# freeduino_hs.net
KiCad netlist of a schematic drawn in EAGLE
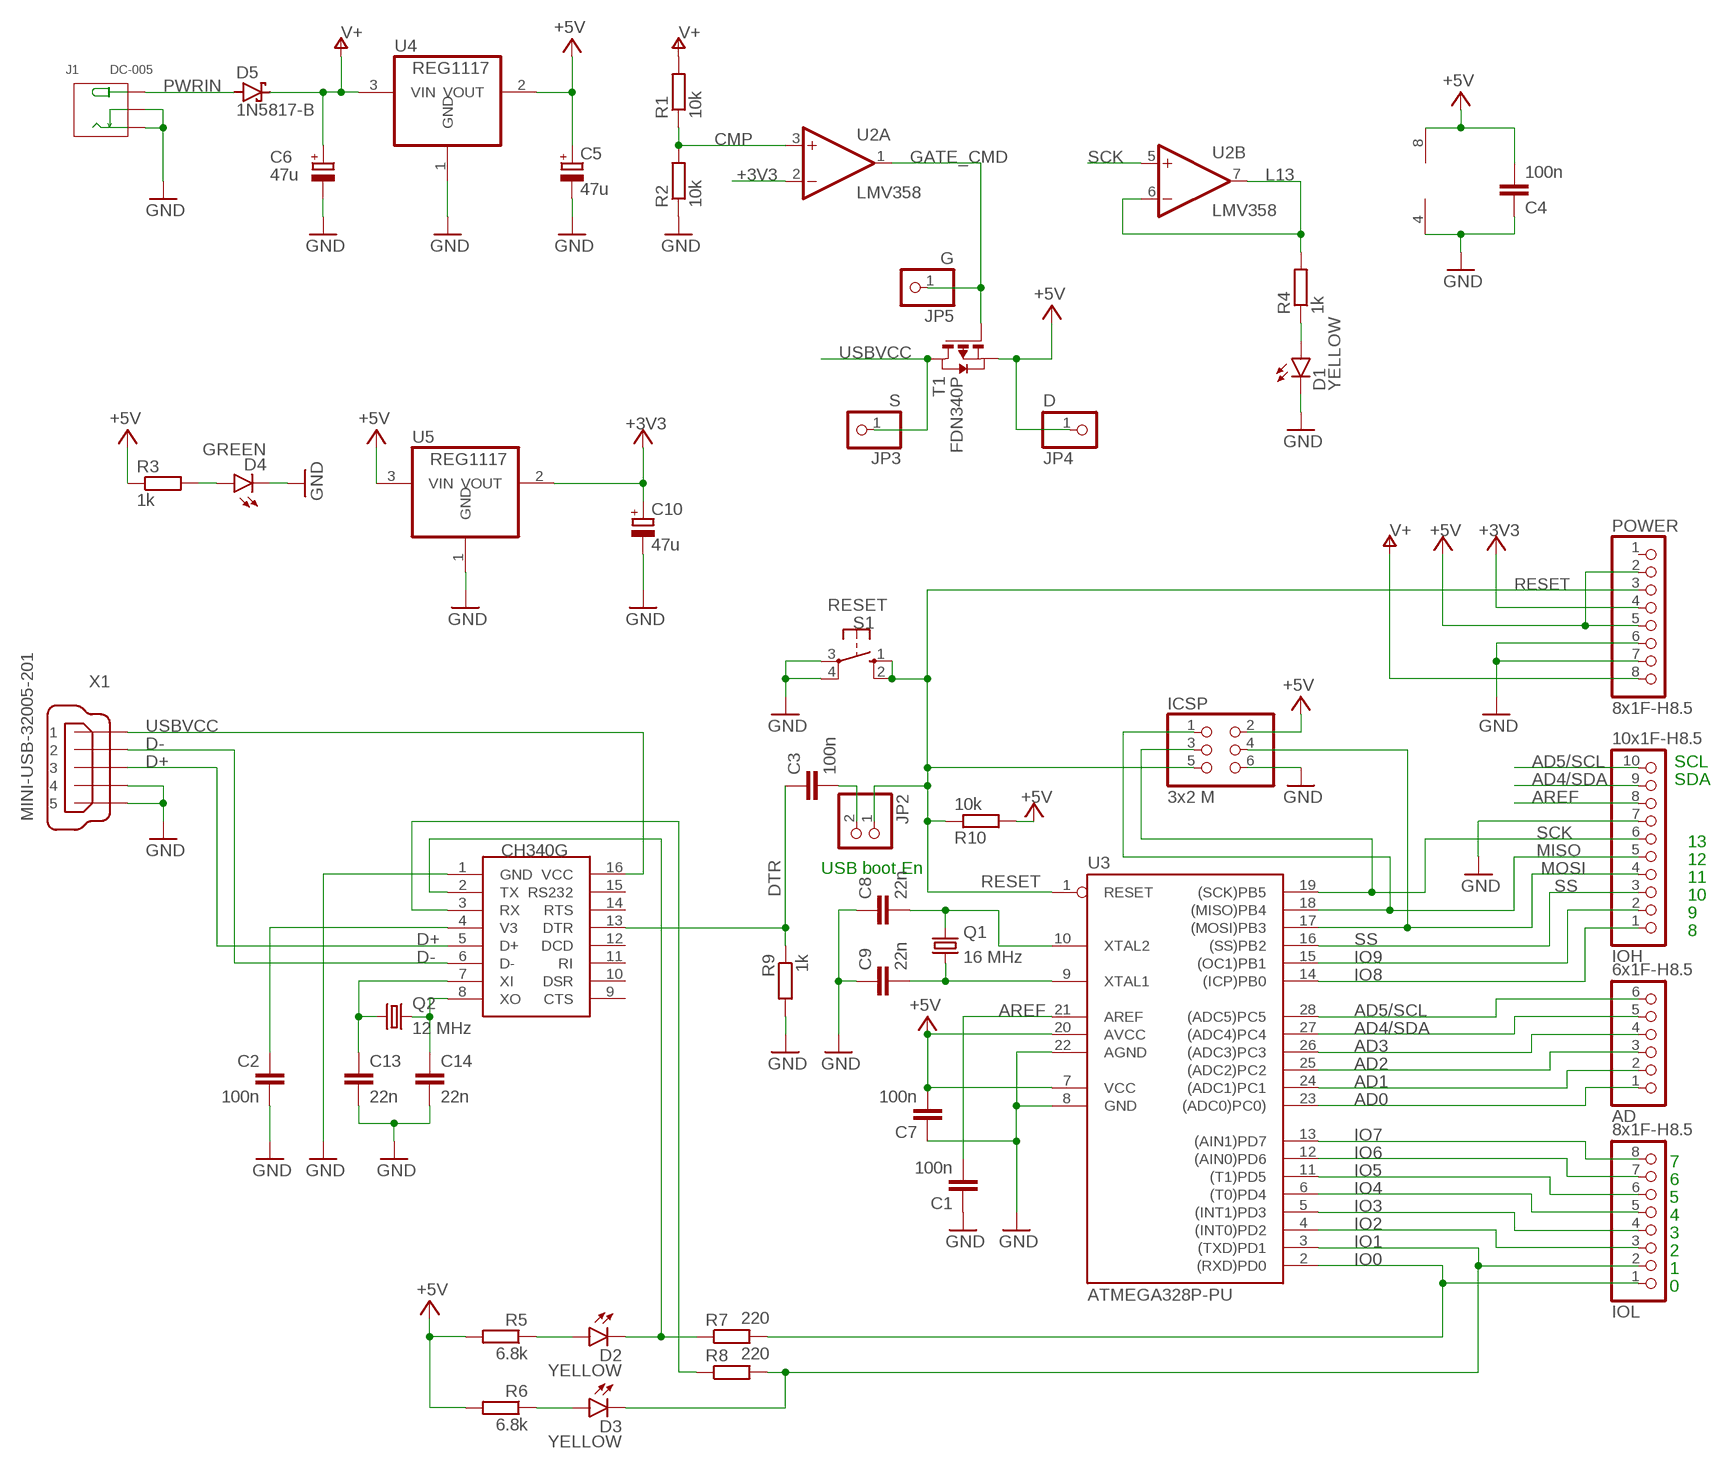
[diagram p0: schematic, sheet 1]

(export (version "E")
  (design (tool "Eeschema 10.0.6"))
  (components
    (comp (ref "AD")
      (value "6x1F-H8.5")
      (footprint "eagle-import:1X06")
      (libsource (lib "eagle-import") (part "PINHD-1X6"))
    )
    (comp (ref "C1")
      (value "100n")
      (footprint "eagle-import:C050-024X044")
      (libsource (lib "eagle-import") (part "C-EU050-024X044"))
    )
    (comp (ref "C2")
      (value "100n")
      (footprint "eagle-import:C050-024X044")
      (libsource (lib "eagle-import") (part "C-EU050-024X044"))
    )
    (comp (ref "C3")
      (value "100n")
      (footprint "eagle-import:C050-024X044")
      (libsource (lib "eagle-import") (part "C-EU050-024X044"))
    )
    (comp (ref "C4")
      (value "100n")
      (footprint "eagle-import:C050-024X044")
      (libsource (lib "eagle-import") (part "C-EU050-024X044"))
    )
    (comp (ref "C5")
      (value "47u")
      (footprint "eagle-import:E2,5-5")
      (libsource (lib "eagle-import") (part "CPOL-EUE2.5-5"))
    )
    (comp (ref "C6")
      (value "47u")
      (footprint "eagle-import:E2,5-5")
      (libsource (lib "eagle-import") (part "CPOL-EUE2.5-5"))
    )
    (comp (ref "C7")
      (value "100n")
      (footprint "eagle-import:C050-024X044")
      (libsource (lib "eagle-import") (part "C-EU050-024X044"))
    )
    (comp (ref "C8")
      (value "22n")
      (footprint "eagle-import:C050-024X044")
      (libsource (lib "eagle-import") (part "C-EU050-024X044"))
    )
    (comp (ref "C9")
      (value "22n")
      (footprint "eagle-import:C050-024X044")
      (libsource (lib "eagle-import") (part "C-EU050-024X044"))
    )
    (comp (ref "C10")
      (value "47u")
      (footprint "eagle-import:E2,5-5")
      (libsource (lib "eagle-import") (part "CPOL-EUE2.5-5"))
    )
    (comp (ref "C13")
      (value "22n")
      (footprint "eagle-import:C050-024X044")
      (libsource (lib "eagle-import") (part "C-EU050-024X044"))
    )
    (comp (ref "C14")
      (value "22n")
      (footprint "eagle-import:C050-024X044")
      (libsource (lib "eagle-import") (part "C-EU050-024X044"))
    )
    (comp (ref "D1")
      (value "YELLOW")
      (footprint "eagle-import:LED3MM")
      (libsource (lib "eagle-import") (part "LED3MM"))
    )
    (comp (ref "D2")
      (value "YELLOW")
      (footprint "eagle-import:LED3MM")
      (libsource (lib "eagle-import") (part "LED3MM"))
    )
    (comp (ref "D3")
      (value "YELLOW")
      (footprint "eagle-import:LED3MM")
      (libsource (lib "eagle-import") (part "LED3MM"))
    )
    (comp (ref "D4")
      (value "GREEN")
      (footprint "eagle-import:LED3MM")
      (libsource (lib "eagle-import") (part "LED3MM"))
    )
    (comp (ref "D5")
      (value "1N5817-B")
      (footprint "eagle-import:DO41-7.6")
      (libsource (lib "eagle-import") (part "1N5817-B"))
    )
    (comp (ref "ICSP")
      (value "3x2 M")
      (footprint "eagle-import:2X03")
      (libsource (lib "eagle-import") (part "PINHD-2X3"))
    )
    (comp (ref "IOH")
      (value "10x1F-H8.5")
      (footprint "eagle-import:1X10")
      (libsource (lib "eagle-import") (part "PINHD-1X10"))
    )
    (comp (ref "IOL")
      (value "8x1F-H8.5")
      (footprint "eagle-import:1X08")
      (libsource (lib "eagle-import") (part "PINHD-1X8"))
    )
    (comp (ref "J1")
      (value "DC-005")
      (footprint "eagle-import:DCJ3P-14.2X11.0X9.0MM")
      (libsource (lib "eagle-import") (part "CONN-POWER-JACK-2.1MM(DC-005)"))
    )
    (comp (ref "JP2")
      (value "PINHD-1X2")
      (footprint "eagle-import:1X02")
      (libsource (lib "eagle-import") (part "PINHD-1X2"))
    )
    (comp (ref "JP3")
      (value "S")
      (footprint "eagle-import:1X01")
      (libsource (lib "eagle-import") (part "PINHD-1X1"))
    )
    (comp (ref "JP4")
      (value "D")
      (footprint "eagle-import:1X01")
      (libsource (lib "eagle-import") (part "PINHD-1X1"))
    )
    (comp (ref "JP5")
      (value "G")
      (footprint "eagle-import:1X01")
      (libsource (lib "eagle-import") (part "PINHD-1X1"))
    )
    (comp (ref "POWER")
      (value "8x1F-H8.5")
      (footprint "eagle-import:1X08")
      (libsource (lib "eagle-import") (part "PINHD-1X8"))
    )
    (comp (ref "Q1")
      (value "16 MHz")
      (footprint "eagle-import:HC49_S")
      (libsource (lib "eagle-import") (part "CRYSTALHC49S"))
    )
    (comp (ref "Q2")
      (value "12 MHz")
      (footprint "eagle-import:HC49_S")
      (libsource (lib "eagle-import") (part "CRYSTALHC49S"))
    )
    (comp (ref "R1")
      (value "10k")
      (footprint "eagle-import:0204_7")
      (libsource (lib "eagle-import") (part "R-EU_0204/7"))
    )
    (comp (ref "R2")
      (value "10k")
      (footprint "eagle-import:0204_7")
      (libsource (lib "eagle-import") (part "R-EU_0204/7"))
    )
    (comp (ref "R3")
      (value "1k")
      (footprint "eagle-import:0204_7")
      (libsource (lib "eagle-import") (part "R-EU_0204/7"))
    )
    (comp (ref "R4")
      (value "1k")
      (footprint "eagle-import:0204_7")
      (libsource (lib "eagle-import") (part "R-EU_0204/7"))
    )
    (comp (ref "R5")
      (value "6.8k")
      (footprint "eagle-import:0204_7")
      (libsource (lib "eagle-import") (part "R-EU_0204/7"))
    )
    (comp (ref "R6")
      (value "6.8k")
      (footprint "eagle-import:0204_7")
      (libsource (lib "eagle-import") (part "R-EU_0204/7"))
    )
    (comp (ref "R7")
      (value "220")
      (footprint "eagle-import:0204_7")
      (libsource (lib "eagle-import") (part "R-EU_0204/7"))
    )
    (comp (ref "R8")
      (value "220")
      (footprint "eagle-import:0204_7")
      (libsource (lib "eagle-import") (part "R-EU_0204/7"))
    )
    (comp (ref "R9")
      (value "1k")
      (footprint "eagle-import:0204_7")
      (libsource (lib "eagle-import") (part "R-EU_0204/7"))
    )
    (comp (ref "R10")
      (value "10k")
      (footprint "eagle-import:0204_7")
      (libsource (lib "eagle-import") (part "R-EU_0204/7"))
    )
    (comp (ref "S1")
      (value "RESET")
      (footprint "eagle-import:B3F-10XX")
      (fields (field (name "MPN") "B3F-1000"))
      (libsource (lib "eagle-import") (part "10-XX"))
    )
    (comp (ref "T1")
      (value "FDN340P")
      (footprint "eagle-import:SOT-23")
      (libsource (lib "eagle-import") (part "PMOSSOT23"))
    )
    (comp (ref "U1")
      (value "CH340G")
      (footprint "eagle-import:SOIC16")
      (libsource (lib "eagle-import") (part "CH340G"))
    )
    (comp (ref "U2")
      (value "LMV358")
      (footprint "eagle-import:SO08")
      (libsource (lib "eagle-import") (part "LMV358?M"))
    )
    (comp (ref "U3")
      (value "ATMEGA328P-PU")
      (footprint "eagle-import:DIL28-3")
      (libsource (lib "eagle-import") (part "ATMEGA328P-PU"))
    )
    (comp (ref "U4")
      (value "REG1117")
      (footprint "eagle-import:SOT223")
      (libsource (lib "eagle-import") (part "REG1117"))
    )
    (comp (ref "U5")
      (value "REG1117")
      (footprint "eagle-import:SOT223")
      (libsource (lib "eagle-import") (part "REG1117"))
    )
    (comp (ref "X1")
      (value "MINI-USB-32005-201")
      (footprint "eagle-import:32005-201")
      (libsource (lib "eagle-import") (part "MINI-USB-32005-201"))
    )
  )
  (nets
    (net (code "1") (name "+3V3") (class "Default")
      (node (ref "C10") (pin "+") (pinfunction "+_+") (pintype "passive"))
      (node (ref "POWER") (pin "4") (pinfunction "4_4") (pintype "passive"))
      (node (ref "U2") (pin "2") (pinfunction "-IN_2") (pintype "input"))
      (node (ref "U5") (pin "2") (pinfunction "VOUT_2") (pintype "output"))
    )
    (net (code "2") (name "+5V") (class "Default")
      (node (ref "C4") (pin "2") (pinfunction "2_2") (pintype "passive"))
      (node (ref "C5") (pin "+") (pinfunction "+_+") (pintype "passive"))
      (node (ref "C7") (pin "2") (pinfunction "2_2") (pintype "passive"))
      (node (ref "ICSP") (pin "2") (pinfunction "2_2") (pintype "passive"))
      (node (ref "JP4") (pin "1") (pinfunction "1_1") (pintype "passive"))
      (node (ref "POWER") (pin "2") (pinfunction "2_2") (pintype "passive"))
      (node (ref "POWER") (pin "5") (pinfunction "5_5") (pintype "passive"))
      (node (ref "R10") (pin "2") (pinfunction "2_2") (pintype "passive"))
      (node (ref "R3") (pin "1") (pinfunction "1_1") (pintype "passive"))
      (node (ref "R5") (pin "2") (pinfunction "2_2") (pintype "passive"))
      (node (ref "R6") (pin "2") (pinfunction "2_2") (pintype "passive"))
      (node (ref "T1") (pin "2") (pinfunction "S_2") (pintype "passive"))
      (node (ref "U2") (pin "8") (pinfunction "V+_8") (pintype "power_in"))
      (node (ref "U3") (pin "20") (pinfunction "AVCC_20") (pintype "power_in"))
      (node (ref "U3") (pin "7") (pinfunction "VCC_7") (pintype "power_in"))
      (node (ref "U4") (pin "2") (pinfunction "VOUT_2") (pintype "output"))
      (node (ref "U5") (pin "3") (pinfunction "VIN_3") (pintype "input"))
    )
    (net (code "3") (name "/AD0") (class "Default")
      (node (ref "AD") (pin "1") (pinfunction "1_1") (pintype "passive"))
      (node (ref "U3") (pin "23") (pinfunction "(ADC0)PC0)_23") (pintype "bidirectional"))
    )
    (net (code "4") (name "/AD1") (class "Default")
      (node (ref "AD") (pin "2") (pinfunction "2_2") (pintype "passive"))
      (node (ref "U3") (pin "24") (pinfunction "(ADC1)PC1_24") (pintype "bidirectional"))
    )
    (net (code "5") (name "/AD2") (class "Default")
      (node (ref "AD") (pin "3") (pinfunction "3_3") (pintype "passive"))
      (node (ref "U3") (pin "25") (pinfunction "(ADC2)PC2_25") (pintype "bidirectional"))
    )
    (net (code "6") (name "/AD3") (class "Default")
      (node (ref "AD") (pin "4") (pinfunction "4_4") (pintype "passive"))
      (node (ref "U3") (pin "26") (pinfunction "(ADC3)PC3_26") (pintype "bidirectional"))
    )
    (net (code "7") (name "/AD4{slash}SDA") (class "Default")
      (node (ref "AD") (pin "5") (pinfunction "5_5") (pintype "passive"))
      (node (ref "IOH") (pin "9") (pinfunction "9_9") (pintype "passive"))
      (node (ref "U3") (pin "27") (pinfunction "(ADC4)PC4_27") (pintype "bidirectional"))
    )
    (net (code "8") (name "/AD5{slash}SCL") (class "Default")
      (node (ref "AD") (pin "6") (pinfunction "6_6") (pintype "passive"))
      (node (ref "IOH") (pin "10") (pinfunction "10_10") (pintype "passive"))
      (node (ref "U3") (pin "28") (pinfunction "(ADC5)PC5_28") (pintype "bidirectional"))
    )
    (net (code "9") (name "/AREF") (class "Default")
      (node (ref "C1") (pin "2") (pinfunction "2_2") (pintype "passive"))
      (node (ref "IOH") (pin "8") (pinfunction "8_8") (pintype "passive"))
      (node (ref "U3") (pin "21") (pinfunction "AREF_21") (pintype "passive"))
    )
    (net (code "10") (name "/CMP") (class "Default")
      (node (ref "R1") (pin "1") (pinfunction "1_1") (pintype "passive"))
      (node (ref "R2") (pin "2") (pinfunction "2_2") (pintype "passive"))
      (node (ref "U2") (pin "3") (pinfunction "+IN_3") (pintype "input"))
    )
    (net (code "11") (name "/D+") (class "Default")
      (node (ref "U1") (pin "5") (pinfunction "D+_5") (pintype "bidirectional"))
      (node (ref "X1") (pin "3") (pinfunction "3_3") (pintype "passive"))
    )
    (net (code "12") (name "/D-") (class "Default")
      (node (ref "U1") (pin "6") (pinfunction "D-_6") (pintype "bidirectional"))
      (node (ref "X1") (pin "2") (pinfunction "2_2") (pintype "passive"))
    )
    (net (code "13") (name "/DTR") (class "Default")
      (node (ref "C3") (pin "1") (pinfunction "1_1") (pintype "passive"))
      (node (ref "R9") (pin "1") (pinfunction "1_1") (pintype "passive"))
      (node (ref "U1") (pin "13") (pinfunction "DTR_13") (pintype "bidirectional"))
    )
    (net (code "14") (name "/GATE_CMD") (class "Default")
      (node (ref "JP5") (pin "1") (pinfunction "1_1") (pintype "passive"))
      (node (ref "T1") (pin "3") (pinfunction "G_3") (pintype "passive"))
      (node (ref "U2") (pin "1") (pinfunction "OUT_1") (pintype "output"))
    )
    (net (code "15") (name "/IO0") (class "Default")
      (node (ref "IOL") (pin "1") (pinfunction "1_1") (pintype "passive"))
      (node (ref "R7") (pin "2") (pinfunction "2_2") (pintype "passive"))
      (node (ref "U3") (pin "2") (pinfunction "(RXD)PD0_2") (pintype "bidirectional"))
    )
    (net (code "16") (name "/IO1") (class "Default")
      (node (ref "D3") (pin "K") (pinfunction "C_K") (pintype "passive"))
      (node (ref "IOL") (pin "2") (pinfunction "2_2") (pintype "passive"))
      (node (ref "R8") (pin "2") (pinfunction "2_2") (pintype "passive"))
      (node (ref "U3") (pin "3") (pinfunction "(TXD)PD1_3") (pintype "bidirectional"))
    )
    (net (code "17") (name "/IO2") (class "Default")
      (node (ref "IOL") (pin "3") (pinfunction "3_3") (pintype "passive"))
      (node (ref "U3") (pin "4") (pinfunction "(INT0)PD2_4") (pintype "bidirectional"))
    )
    (net (code "18") (name "/IO3") (class "Default")
      (node (ref "IOL") (pin "4") (pinfunction "4_4") (pintype "passive"))
      (node (ref "U3") (pin "5") (pinfunction "(INT1)PD3_5") (pintype "bidirectional"))
    )
    (net (code "19") (name "/IO4") (class "Default")
      (node (ref "IOL") (pin "5") (pinfunction "5_5") (pintype "passive"))
      (node (ref "U3") (pin "6") (pinfunction "(T0)PD4_6") (pintype "bidirectional"))
    )
    (net (code "20") (name "/IO5") (class "Default")
      (node (ref "IOL") (pin "6") (pinfunction "6_6") (pintype "passive"))
      (node (ref "U3") (pin "11") (pinfunction "(T1)PD5_11") (pintype "bidirectional"))
    )
    (net (code "21") (name "/IO6") (class "Default")
      (node (ref "IOL") (pin "7") (pinfunction "7_7") (pintype "passive"))
      (node (ref "U3") (pin "12") (pinfunction "(AIN0)PD6_12") (pintype "bidirectional"))
    )
    (net (code "22") (name "/IO7") (class "Default")
      (node (ref "IOL") (pin "8") (pinfunction "8_8") (pintype "passive"))
      (node (ref "U3") (pin "13") (pinfunction "(AIN1)PD7_13") (pintype "bidirectional"))
    )
    (net (code "23") (name "/IO8") (class "Default")
      (node (ref "IOH") (pin "1") (pinfunction "1_1") (pintype "passive"))
      (node (ref "U3") (pin "14") (pinfunction "(ICP)PB0_14") (pintype "bidirectional"))
    )
    (net (code "24") (name "/IO9") (class "Default")
      (node (ref "IOH") (pin "2") (pinfunction "2_2") (pintype "passive"))
      (node (ref "U3") (pin "15") (pinfunction "(OC1)PB1_15") (pintype "bidirectional"))
    )
    (net (code "25") (name "/L13") (class "Default")
      (node (ref "R4") (pin "2") (pinfunction "2_2") (pintype "passive"))
      (node (ref "U2") (pin "6") (pinfunction "-IN_6") (pintype "input"))
      (node (ref "U2") (pin "7") (pinfunction "OUT_7") (pintype "output"))
    )
    (net (code "26") (name "/MISO") (class "Default")
      (node (ref "ICSP") (pin "1") (pinfunction "1_1") (pintype "passive"))
      (node (ref "IOH") (pin "5") (pinfunction "5_5") (pintype "passive"))
      (node (ref "U3") (pin "18") (pinfunction "(MISO)PB4_18") (pintype "bidirectional"))
    )
    (net (code "27") (name "/MOSI") (class "Default")
      (node (ref "ICSP") (pin "4") (pinfunction "4_4") (pintype "passive"))
      (node (ref "IOH") (pin "4") (pinfunction "4_4") (pintype "passive"))
      (node (ref "U3") (pin "17") (pinfunction "(MOSI)PB3_17") (pintype "bidirectional"))
    )
    (net (code "28") (name "/PWRIN") (class "Default")
      (node (ref "D5") (pin "A") (pinfunction "A_A") (pintype "passive"))
      (node (ref "J1") (pin "+") (pinfunction "+_+") (pintype "bidirectional"))
    )
    (net (code "29") (name "/RESET") (class "Default")
      (node (ref "ICSP") (pin "5") (pinfunction "5_5") (pintype "passive"))
      (node (ref "JP2") (pin "1") (pinfunction "1_1") (pintype "passive"))
      (node (ref "POWER") (pin "3") (pinfunction "3_3") (pintype "passive"))
      (node (ref "R10") (pin "1") (pinfunction "1_1") (pintype "passive"))
      (node (ref "S1") (pin "1") (pinfunction "S_1") (pintype "passive"))
      (node (ref "S1") (pin "2") (pinfunction "S1_2") (pintype "passive"))
      (node (ref "U3") (pin "1") (pinfunction "RESET_1") (pintype "input"))
    )
    (net (code "30") (name "/SCK") (class "Default")
      (node (ref "ICSP") (pin "3") (pinfunction "3_3") (pintype "passive"))
      (node (ref "IOH") (pin "6") (pinfunction "6_6") (pintype "passive"))
      (node (ref "U2") (pin "5") (pinfunction "+IN_5") (pintype "input"))
      (node (ref "U3") (pin "19") (pinfunction "(SCK)PB5_19") (pintype "bidirectional"))
    )
    (net (code "31") (name "/SS") (class "Default")
      (node (ref "IOH") (pin "3") (pinfunction "3_3") (pintype "passive"))
      (node (ref "U3") (pin "16") (pinfunction "(SS)PB2_16") (pintype "bidirectional"))
    )
    (net (code "32") (name "/USBVCC") (class "Default")
      (node (ref "JP3") (pin "1") (pinfunction "1_1") (pintype "passive"))
      (node (ref "T1") (pin "1") (pinfunction "D_1") (pintype "passive"))
      (node (ref "U1") (pin "16") (pinfunction "VCC_16") (pintype "bidirectional"))
      (node (ref "X1") (pin "1") (pinfunction "1_1") (pintype "passive"))
    )
    (net (code "33") (name "GND") (class "Default")
      (node (ref "C1") (pin "1") (pinfunction "1_1") (pintype "passive"))
      (node (ref "C10") (pin "-") (pinfunction "-_-") (pintype "passive"))
      (node (ref "C13") (pin "2") (pinfunction "2_2") (pintype "passive"))
      (node (ref "C14") (pin "2") (pinfunction "2_2") (pintype "passive"))
      (node (ref "C2") (pin "2") (pinfunction "2_2") (pintype "passive"))
      (node (ref "C4") (pin "1") (pinfunction "1_1") (pintype "passive"))
      (node (ref "C5") (pin "-") (pinfunction "-_-") (pintype "passive"))
      (node (ref "C6") (pin "-") (pinfunction "-_-") (pintype "passive"))
      (node (ref "C7") (pin "1") (pinfunction "1_1") (pintype "passive"))
      (node (ref "C8") (pin "1") (pinfunction "1_1") (pintype "passive"))
      (node (ref "C9") (pin "1") (pinfunction "1_1") (pintype "passive"))
      (node (ref "D1") (pin "K") (pinfunction "C_K") (pintype "passive"))
      (node (ref "D4") (pin "K") (pinfunction "C_K") (pintype "passive"))
      (node (ref "ICSP") (pin "6") (pinfunction "6_6") (pintype "passive"))
      (node (ref "IOH") (pin "7") (pinfunction "7_7") (pintype "passive"))
      (node (ref "J1") (pin "-1") (pinfunction "-_-1") (pintype "bidirectional"))
      (node (ref "J1") (pin "-2") (pinfunction "CDN_-2") (pintype "bidirectional"))
      (node (ref "POWER") (pin "6") (pinfunction "6_6") (pintype "passive"))
      (node (ref "POWER") (pin "7") (pinfunction "7_7") (pintype "passive"))
      (node (ref "R2") (pin "1") (pinfunction "1_1") (pintype "passive"))
      (node (ref "R9") (pin "2") (pinfunction "2_2") (pintype "passive"))
      (node (ref "S1") (pin "3") (pinfunction "P_3") (pintype "passive"))
      (node (ref "S1") (pin "4") (pinfunction "P1_4") (pintype "passive"))
      (node (ref "U1") (pin "1") (pinfunction "GND_1") (pintype "bidirectional"))
      (node (ref "U2") (pin "4") (pinfunction "V-_4") (pintype "power_in"))
      (node (ref "U3") (pin "22") (pinfunction "AGND_22") (pintype "power_in"))
      (node (ref "U3") (pin "8") (pinfunction "GND_8") (pintype "power_in"))
      (node (ref "U4") (pin "1") (pinfunction "GND_1") (pintype "power_in"))
      (node (ref "U5") (pin "1") (pinfunction "GND_1") (pintype "power_in"))
      (node (ref "X1") (pin "4") (pinfunction "4_4") (pintype "passive"))
      (node (ref "X1") (pin "5") (pinfunction "5_5") (pintype "passive"))
    )
    (net (code "34") (name "Net-(C3-Pad2)") (class "Default")
      (node (ref "C3") (pin "2") (pinfunction "2_2") (pintype "passive"))
      (node (ref "JP2") (pin "2") (pinfunction "2_2") (pintype "passive"))
    )
    (net (code "35") (name "Net-(D1-PadA)") (class "Default")
      (node (ref "D1") (pin "A") (pinfunction "A_A") (pintype "passive"))
      (node (ref "R4") (pin "1") (pinfunction "1_1") (pintype "passive"))
    )
    (net (code "36") (name "Net-(D2-C)") (class "Default")
      (node (ref "D2") (pin "K") (pinfunction "C_K") (pintype "passive"))
      (node (ref "R7") (pin "1") (pinfunction "1_1") (pintype "passive"))
      (node (ref "U1") (pin "2") (pinfunction "TX_2") (pintype "bidirectional"))
    )
    (net (code "37") (name "Net-(D2-PadA)") (class "Default")
      (node (ref "D2") (pin "A") (pinfunction "A_A") (pintype "passive"))
      (node (ref "R5") (pin "1") (pinfunction "1_1") (pintype "passive"))
    )
    (net (code "38") (name "Net-(D3-PadA)") (class "Default")
      (node (ref "D3") (pin "A") (pinfunction "A_A") (pintype "passive"))
      (node (ref "R6") (pin "1") (pinfunction "1_1") (pintype "passive"))
    )
    (net (code "39") (name "Net-(D4-PadA)") (class "Default")
      (node (ref "D4") (pin "A") (pinfunction "A_A") (pintype "passive"))
      (node (ref "R3") (pin "2") (pinfunction "2_2") (pintype "passive"))
    )
    (net (code "40") (name "Net-(U1-RX)") (class "Default")
      (node (ref "R8") (pin "1") (pinfunction "1_1") (pintype "passive"))
      (node (ref "U1") (pin "3") (pinfunction "RX_3") (pintype "bidirectional"))
    )
    (net (code "41") (name "Net-(U1-V3)") (class "Default")
      (node (ref "C2") (pin "1") (pinfunction "1_1") (pintype "passive"))
      (node (ref "U1") (pin "4") (pinfunction "V3_4") (pintype "bidirectional"))
    )
    (net (code "42") (name "Net-(U1-XI)") (class "Default")
      (node (ref "C13") (pin "1") (pinfunction "1_1") (pintype "passive"))
      (node (ref "Q2") (pin "2") (pinfunction "2_2") (pintype "passive"))
      (node (ref "U1") (pin "7") (pinfunction "XI_7") (pintype "bidirectional"))
    )
    (net (code "43") (name "Net-(U1-XO)") (class "Default")
      (node (ref "C14") (pin "1") (pinfunction "1_1") (pintype "passive"))
      (node (ref "Q2") (pin "1") (pinfunction "1_1") (pintype "passive"))
      (node (ref "U1") (pin "8") (pinfunction "XO_8") (pintype "bidirectional"))
    )
    (net (code "44") (name "Net-(U3-XTAL1)") (class "Default")
      (node (ref "C9") (pin "2") (pinfunction "2_2") (pintype "passive"))
      (node (ref "Q1") (pin "1") (pinfunction "1_1") (pintype "passive"))
      (node (ref "U3") (pin "9") (pinfunction "XTAL1_9") (pintype "bidirectional"))
    )
    (net (code "45") (name "Net-(U3-XTAL2)") (class "Default")
      (node (ref "C8") (pin "2") (pinfunction "2_2") (pintype "passive"))
      (node (ref "Q1") (pin "2") (pinfunction "2_2") (pintype "passive"))
      (node (ref "U3") (pin "10") (pinfunction "XTAL2_10") (pintype "bidirectional"))
    )
    (net (code "46") (name "V+") (class "Default")
      (node (ref "C6") (pin "+") (pinfunction "+_+") (pintype "passive"))
      (node (ref "D5") (pin "C") (pinfunction "C_C") (pintype "passive"))
      (node (ref "POWER") (pin "8") (pinfunction "8_8") (pintype "passive"))
      (node (ref "R1") (pin "2") (pinfunction "2_2") (pintype "passive"))
      (node (ref "U4") (pin "3") (pinfunction "VIN_3") (pintype "input"))
    )
    (net (code "47") (name "unconnected-(POWER-Pad1)") (class "Default")
      (node (ref "POWER") (pin "1") (pinfunction "1_1") (pintype "passive"))
    )
    (net (code "48") (name "unconnected-(U1-CTS-Pad9)") (class "Default")
      (node (ref "U1") (pin "9") (pinfunction "CTS_9") (pintype "bidirectional"))
    )
    (net (code "49") (name "unconnected-(U1-DCD-Pad12)") (class "Default")
      (node (ref "U1") (pin "12") (pinfunction "DCD_12") (pintype "bidirectional"))
    )
    (net (code "50") (name "unconnected-(U1-DSR-Pad10)") (class "Default")
      (node (ref "U1") (pin "10") (pinfunction "DSR_10") (pintype "bidirectional"))
    )
    (net (code "51") (name "unconnected-(U1-RI-Pad11)") (class "Default")
      (node (ref "U1") (pin "11") (pinfunction "RI_11") (pintype "bidirectional"))
    )
    (net (code "52") (name "unconnected-(U1-RS232-Pad15)") (class "Default")
      (node (ref "U1") (pin "15") (pinfunction "RS232_15") (pintype "bidirectional"))
    )
    (net (code "53") (name "unconnected-(U1-RTS-Pad14)") (class "Default")
      (node (ref "U1") (pin "14") (pinfunction "RTS_14") (pintype "bidirectional"))
    )
  )
)
